# SOC_DISPLAY.net
KiCad netlist of a schematic drawn in Altium Designer
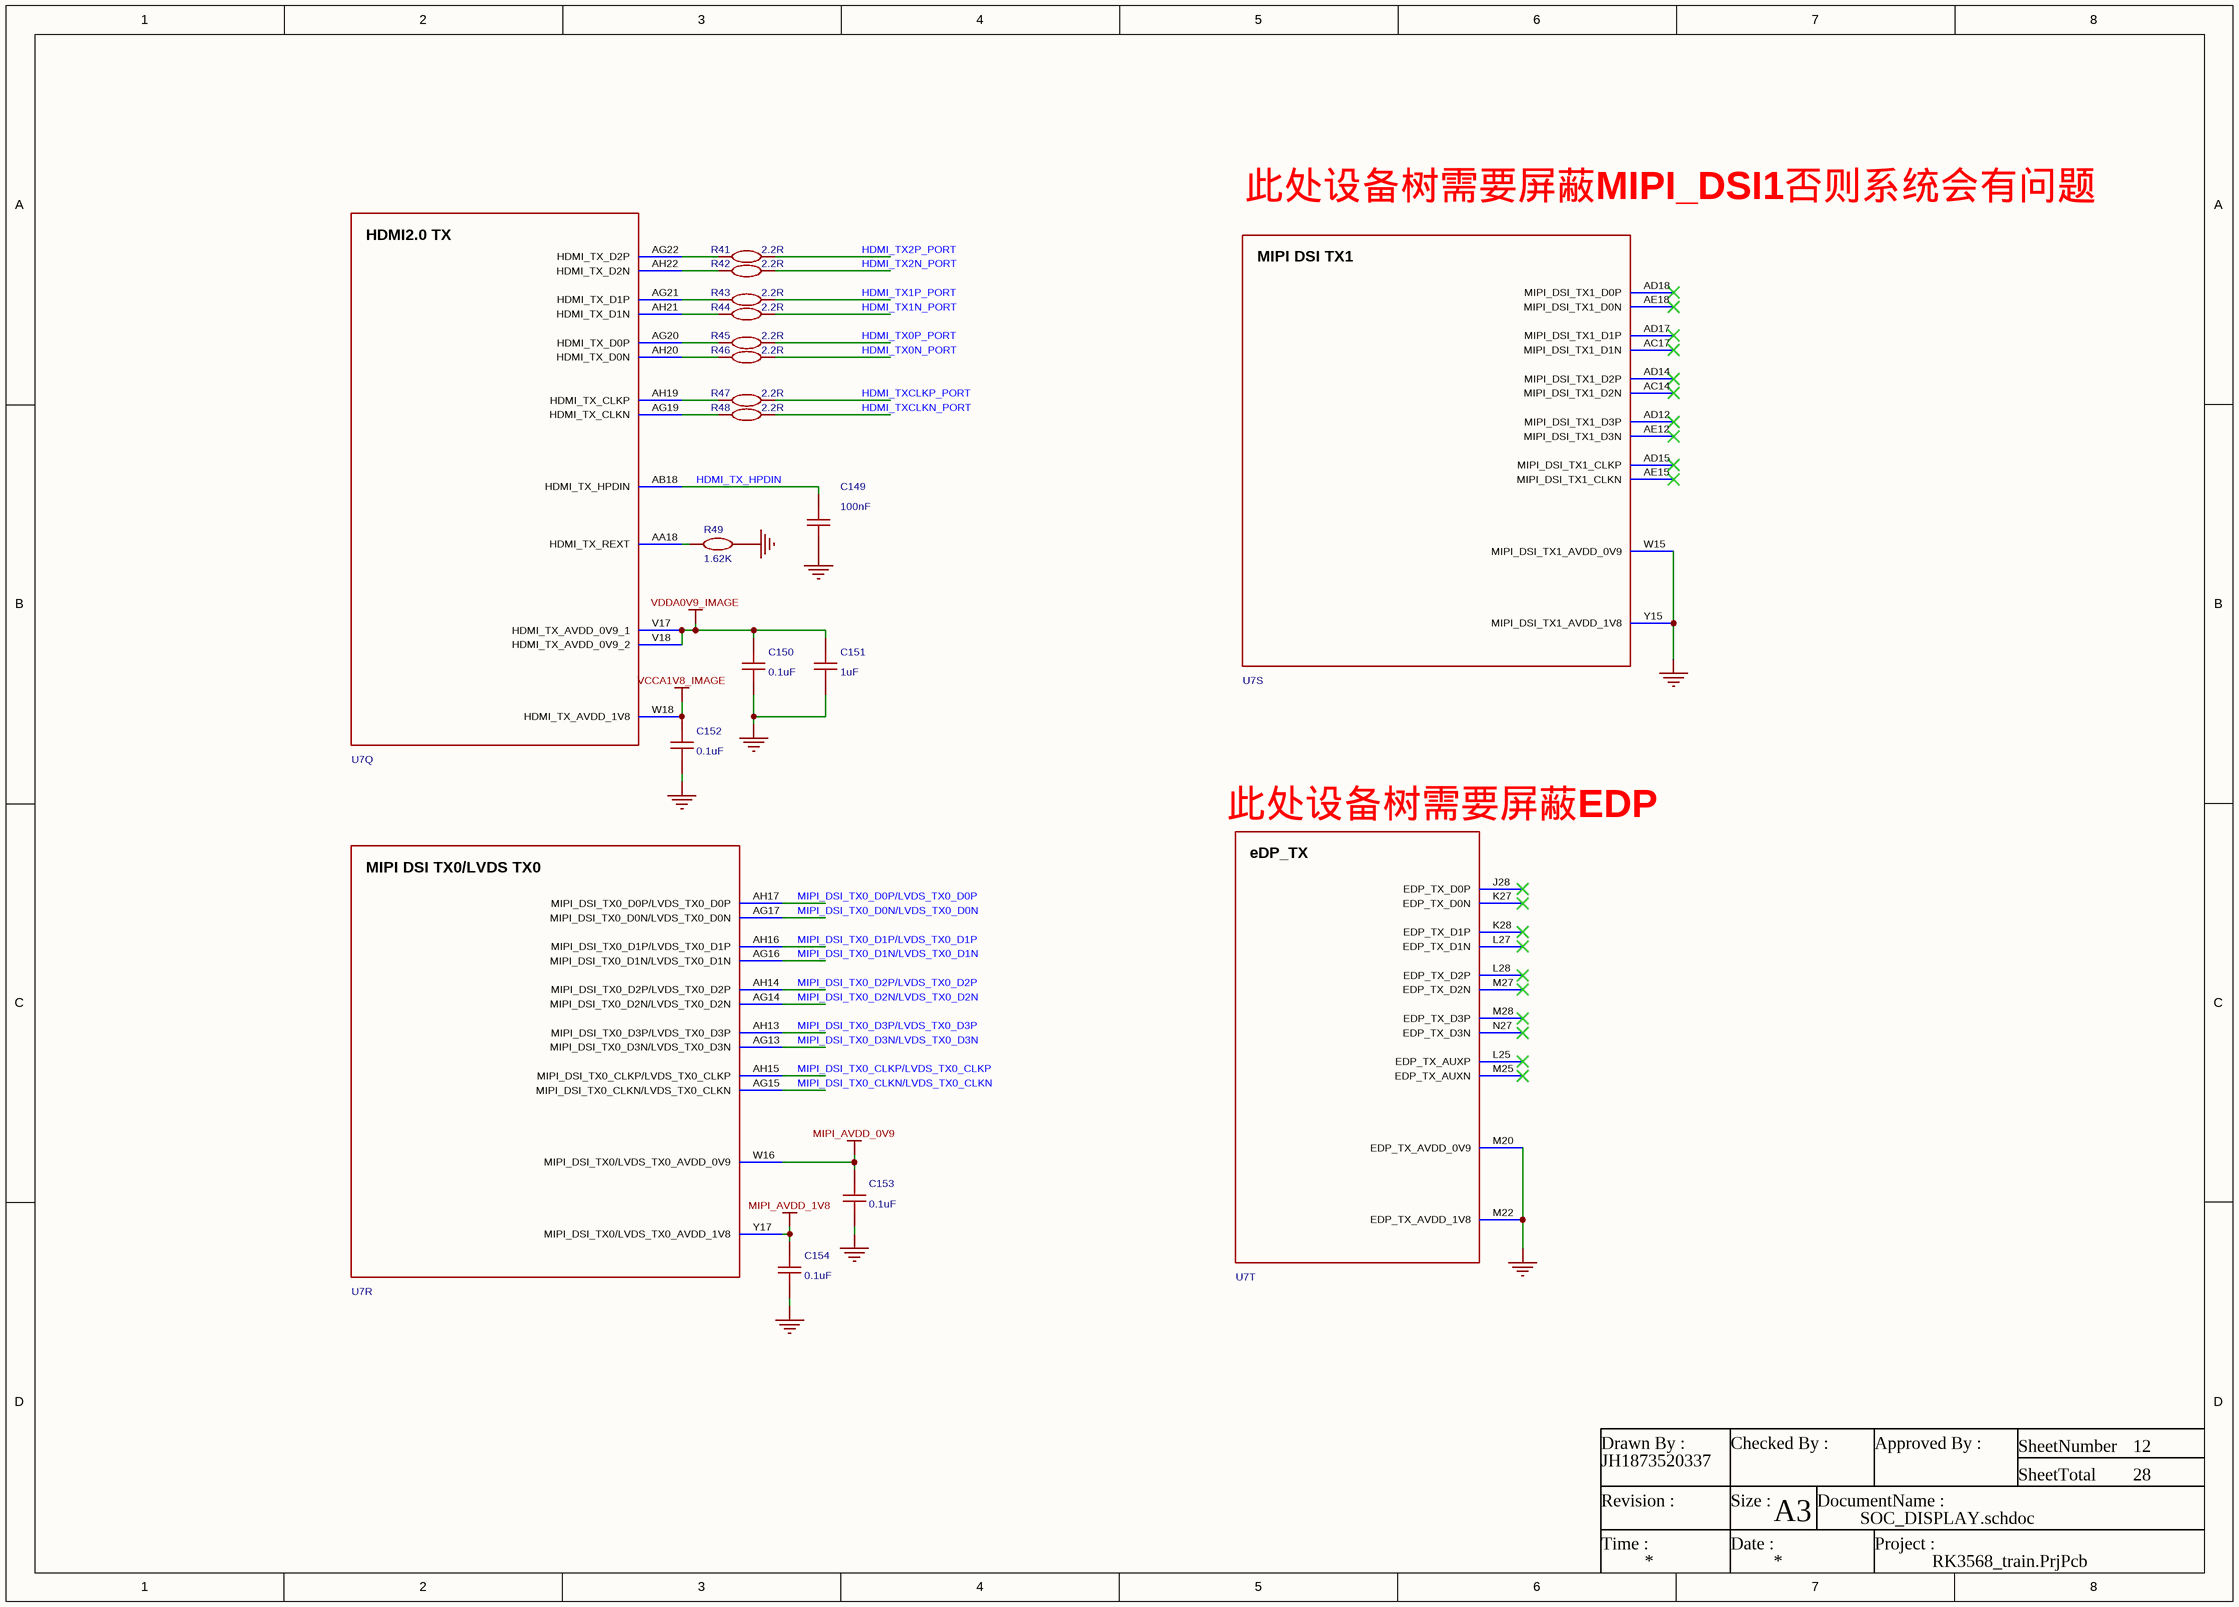
[diagram p0: SOC_DISPLAY.schdoc]

(export (version "E")
  (design (tool "Eeschema 10.0.6"))
  (components
    (comp (ref "C149")
      (value "100nF")
      (footprint "C0201")
      (description "容值:4.7uF;精度:±20%;额定电压:6.3V;温度系数:X5R;")
      (fields
        (field (name "MANUFACTURER") "muRata(村田)")
        (field (name "MANUFACTURERPART") "GRM035R60J475ME15D")
      )
      (libsource (lib "altium-import") (part "root_0_GRM035R60J475ME15D_"))
    )
    (comp (ref "C150")
      (value "0.1uF")
      (footprint "C0201")
      (description "容值:4.7uF;精度:±20%;额定电压:6.3V;温度系数:X5R;")
      (fields
        (field (name "MANUFACTURER") "muRata(村田)")
        (field (name "MANUFACTURERPART") "GRM035R60J475ME15D")
      )
      (libsource (lib "altium-import") (part "root_0_GRM035R60J475ME15D_"))
    )
    (comp (ref "C151")
      (value "1uF")
      (footprint "C0201")
      (description "容值:4.7uF;精度:±20%;额定电压:6.3V;温度系数:X5R;")
      (fields
        (field (name "MANUFACTURER") "muRata(村田)")
        (field (name "MANUFACTURERPART") "GRM035R60J475ME15D")
      )
      (libsource (lib "altium-import") (part "root_0_GRM035R60J475ME15D_"))
    )
    (comp (ref "C152")
      (value "0.1uF")
      (footprint "C0201")
      (description "容值:4.7uF;精度:±20%;额定电压:6.3V;温度系数:X5R;")
      (fields
        (field (name "MANUFACTURER") "muRata(村田)")
        (field (name "MANUFACTURERPART") "GRM035R60J475ME15D")
      )
      (libsource (lib "altium-import") (part "root_0_GRM035R60J475ME15D_"))
    )
    (comp (ref "C153")
      (value "0.1uF")
      (footprint "C0201")
      (description "容值:4.7uF;精度:±20%;额定电压:6.3V;温度系数:X5R;")
      (fields
        (field (name "MANUFACTURER") "muRata(村田)")
        (field (name "MANUFACTURERPART") "GRM035R60J475ME15D")
      )
      (libsource (lib "altium-import") (part "root_0_GRM035R60J475ME15D_"))
    )
    (comp (ref "C154")
      (value "0.1uF")
      (footprint "C0201")
      (description "容值:4.7uF;精度:±20%;额定电压:6.3V;温度系数:X5R;")
      (fields
        (field (name "MANUFACTURER") "muRata(村田)")
        (field (name "MANUFACTURERPART") "GRM035R60J475ME15D")
      )
      (libsource (lib "altium-import") (part "root_0_GRM035R60J475ME15D_"))
    )
    (comp (ref "R41")
      (value "2.2R")
      (footprint "R0201")
      (libsource (lib "altium-import") (part "root_0_Res_0201_"))
    )
    (comp (ref "R42")
      (value "2.2R")
      (footprint "R0201")
      (libsource (lib "altium-import") (part "root_0_Res_0201_"))
    )
    (comp (ref "R43")
      (value "2.2R")
      (footprint "R0201")
      (libsource (lib "altium-import") (part "root_0_Res_0201_"))
    )
    (comp (ref "R44")
      (value "2.2R")
      (footprint "R0201")
      (libsource (lib "altium-import") (part "root_0_Res_0201_"))
    )
    (comp (ref "R45")
      (value "2.2R")
      (footprint "R0201")
      (libsource (lib "altium-import") (part "root_0_Res_0201_"))
    )
    (comp (ref "R46")
      (value "2.2R")
      (footprint "R0201")
      (libsource (lib "altium-import") (part "root_0_Res_0201_"))
    )
    (comp (ref "R47")
      (value "2.2R")
      (footprint "R0201")
      (libsource (lib "altium-import") (part "root_0_Res_0201_"))
    )
    (comp (ref "R48")
      (value "2.2R")
      (footprint "R0201")
      (libsource (lib "altium-import") (part "root_0_Res_0201_"))
    )
    (comp (ref "R49")
      (value "1.62K")
      (footprint "R0201")
      (libsource (lib "altium-import") (part "root_0_Res_0201_"))
    )
    (comp (ref "U7")
      (value "RK3568")
      (footprint "BGA-636_L19.0-W19.0-P0.65-BL")
      (libsource (lib "altium-import") (part "root_0_RK3568_"))
    )
  )
  (nets
    (net (code "1") (name "/HDMI_TX0N_PORT") (class "Default")
      (node (ref "R46") (pin "2") (pinfunction "2_2") (pintype "passive"))
    )
    (net (code "2") (name "/HDMI_TX0P_PORT") (class "Default")
      (node (ref "R45") (pin "2") (pinfunction "2_2") (pintype "passive"))
    )
    (net (code "3") (name "/HDMI_TX1N_PORT") (class "Default")
      (node (ref "R44") (pin "2") (pinfunction "2_2") (pintype "passive"))
    )
    (net (code "4") (name "/HDMI_TX1P_PORT") (class "Default")
      (node (ref "R43") (pin "2") (pinfunction "2_2") (pintype "passive"))
    )
    (net (code "5") (name "/HDMI_TX2N_PORT") (class "Default")
      (node (ref "R42") (pin "2") (pinfunction "2_2") (pintype "passive"))
    )
    (net (code "6") (name "/HDMI_TX2P_PORT") (class "Default")
      (node (ref "R41") (pin "2") (pinfunction "2_2") (pintype "passive"))
    )
    (net (code "7") (name "/HDMI_TXCLKN_PORT") (class "Default")
      (node (ref "R48") (pin "2") (pinfunction "2_2") (pintype "passive"))
    )
    (net (code "8") (name "/HDMI_TXCLKP_PORT") (class "Default")
      (node (ref "R47") (pin "2") (pinfunction "2_2") (pintype "passive"))
    )
    (net (code "9") (name "/HDMI_TX_HPDIN") (class "Default")
      (node (ref "C149") (pin "2") (pinfunction "2_2") (pintype "passive"))
      (node (ref "U7") (pin "AB18") (pinfunction "HDMI_TX_HPDIN_AB18") (pintype "passive"))
    )
    (net (code "10") (name "/MIPI_DSI_TX0_CLKN{slash}LVDS_TX0_CLKN") (class "Default")
      (node (ref "U7") (pin "AG15") (pinfunction "MIPI_DSI_TX0_CLKN/LVDS_TX0_CLKN_AG15") (pintype "passive"))
    )
    (net (code "11") (name "/MIPI_DSI_TX0_CLKP{slash}LVDS_TX0_CLKP") (class "Default")
      (node (ref "U7") (pin "AH15") (pinfunction "MIPI_DSI_TX0_CLKP/LVDS_TX0_CLKP_AH15") (pintype "passive"))
    )
    (net (code "12") (name "/MIPI_DSI_TX0_D0N{slash}LVDS_TX0_D0N") (class "Default")
      (node (ref "U7") (pin "AG17") (pinfunction "MIPI_DSI_TX0_D0N/LVDS_TX0_D0N_AG17") (pintype "passive"))
    )
    (net (code "13") (name "/MIPI_DSI_TX0_D0P{slash}LVDS_TX0_D0P") (class "Default")
      (node (ref "U7") (pin "AH17") (pinfunction "MIPI_DSI_TX0_D0P/LVDS_TX0_D0P_AH17") (pintype "passive"))
    )
    (net (code "14") (name "/MIPI_DSI_TX0_D1N{slash}LVDS_TX0_D1N") (class "Default")
      (node (ref "U7") (pin "AG16") (pinfunction "MIPI_DSI_TX0_D1N/LVDS_TX0_D1N_AG16") (pintype "passive"))
    )
    (net (code "15") (name "/MIPI_DSI_TX0_D1P{slash}LVDS_TX0_D1P") (class "Default")
      (node (ref "U7") (pin "AH16") (pinfunction "MIPI_DSI_TX0_D1P/LVDS_TX0_D1P_AH16") (pintype "passive"))
    )
    (net (code "16") (name "/MIPI_DSI_TX0_D2N{slash}LVDS_TX0_D2N") (class "Default")
      (node (ref "U7") (pin "AG14") (pinfunction "MIPI_DSI_TX0_D2N/LVDS_TX0_D2N_AG14") (pintype "passive"))
    )
    (net (code "17") (name "/MIPI_DSI_TX0_D2P{slash}LVDS_TX0_D2P") (class "Default")
      (node (ref "U7") (pin "AH14") (pinfunction "MIPI_DSI_TX0_D2P/LVDS_TX0_D2P_AH14") (pintype "passive"))
    )
    (net (code "18") (name "/MIPI_DSI_TX0_D3N{slash}LVDS_TX0_D3N") (class "Default")
      (node (ref "U7") (pin "AG13") (pinfunction "MIPI_DSI_TX0_D3N/LVDS_TX0_D3N_AG13") (pintype "passive"))
    )
    (net (code "19") (name "/MIPI_DSI_TX0_D3P{slash}LVDS_TX0_D3P") (class "Default")
      (node (ref "U7") (pin "AH13") (pinfunction "MIPI_DSI_TX0_D3P/LVDS_TX0_D3P_AH13") (pintype "passive"))
    )
    (net (code "20") (name "GND") (class "Default")
      (node (ref "C149") (pin "1") (pinfunction "1_1") (pintype "passive"))
      (node (ref "C150") (pin "1") (pinfunction "1_1") (pintype "passive"))
      (node (ref "C151") (pin "1") (pinfunction "1_1") (pintype "passive"))
      (node (ref "C152") (pin "1") (pinfunction "1_1") (pintype "passive"))
      (node (ref "C153") (pin "1") (pinfunction "1_1") (pintype "passive"))
      (node (ref "C154") (pin "1") (pinfunction "1_1") (pintype "passive"))
      (node (ref "R49") (pin "2") (pinfunction "2_2") (pintype "passive"))
      (node (ref "U7") (pin "M20") (pinfunction "EDP_TX_AVDD_0V9_M20") (pintype "passive"))
      (node (ref "U7") (pin "M22") (pinfunction "EDP_TX_AVDD_1V8_M22") (pintype "passive"))
      (node (ref "U7") (pin "W15") (pinfunction "MIPI_DSI_TX1_AVDD_0V9_W15") (pintype "passive"))
      (node (ref "U7") (pin "Y15") (pinfunction "MIPI_DSI_TX1_AVDD_1V8_Y15") (pintype "passive"))
    )
    (net (code "21") (name "MIPI_AVDD_0V9") (class "Default")
      (node (ref "C153") (pin "2") (pinfunction "2_2") (pintype "passive"))
      (node (ref "U7") (pin "W16") (pinfunction "MIPI_DSI_TX0/LVDS_TX0_AVDD_0V9_W16") (pintype "passive"))
    )
    (net (code "22") (name "MIPI_AVDD_1V8") (class "Default")
      (node (ref "C154") (pin "2") (pinfunction "2_2") (pintype "passive"))
      (node (ref "U7") (pin "Y17") (pinfunction "MIPI_DSI_TX0/LVDS_TX0_AVDD_1V8_Y17") (pintype "passive"))
    )
    (net (code "23") (name "Net-(U7Q-HDMI_TX_CLKN)") (class "Default")
      (node (ref "R48") (pin "1") (pinfunction "1_1") (pintype "passive"))
      (node (ref "U7") (pin "AG19") (pinfunction "HDMI_TX_CLKN_AG19") (pintype "passive"))
    )
    (net (code "24") (name "Net-(U7Q-HDMI_TX_CLKP)") (class "Default")
      (node (ref "R47") (pin "1") (pinfunction "1_1") (pintype "passive"))
      (node (ref "U7") (pin "AH19") (pinfunction "HDMI_TX_CLKP_AH19") (pintype "passive"))
    )
    (net (code "25") (name "Net-(U7Q-HDMI_TX_D0N)") (class "Default")
      (node (ref "R46") (pin "1") (pinfunction "1_1") (pintype "passive"))
      (node (ref "U7") (pin "AH20") (pinfunction "HDMI_TX_D0N_AH20") (pintype "passive"))
    )
    (net (code "26") (name "Net-(U7Q-HDMI_TX_D0P)") (class "Default")
      (node (ref "R45") (pin "1") (pinfunction "1_1") (pintype "passive"))
      (node (ref "U7") (pin "AG20") (pinfunction "HDMI_TX_D0P_AG20") (pintype "passive"))
    )
    (net (code "27") (name "Net-(U7Q-HDMI_TX_D1N)") (class "Default")
      (node (ref "R44") (pin "1") (pinfunction "1_1") (pintype "passive"))
      (node (ref "U7") (pin "AH21") (pinfunction "HDMI_TX_D1N_AH21") (pintype "passive"))
    )
    (net (code "28") (name "Net-(U7Q-HDMI_TX_D1P)") (class "Default")
      (node (ref "R43") (pin "1") (pinfunction "1_1") (pintype "passive"))
      (node (ref "U7") (pin "AG21") (pinfunction "HDMI_TX_D1P_AG21") (pintype "passive"))
    )
    (net (code "29") (name "Net-(U7Q-HDMI_TX_D2N)") (class "Default")
      (node (ref "R42") (pin "1") (pinfunction "1_1") (pintype "passive"))
      (node (ref "U7") (pin "AH22") (pinfunction "HDMI_TX_D2N_AH22") (pintype "passive"))
    )
    (net (code "30") (name "Net-(U7Q-HDMI_TX_D2P)") (class "Default")
      (node (ref "R41") (pin "1") (pinfunction "1_1") (pintype "passive"))
      (node (ref "U7") (pin "AG22") (pinfunction "HDMI_TX_D2P_AG22") (pintype "passive"))
    )
    (net (code "31") (name "Net-(U7Q-HDMI_TX_REXT)") (class "Default")
      (node (ref "R49") (pin "1") (pinfunction "1_1") (pintype "passive"))
      (node (ref "U7") (pin "AA18") (pinfunction "HDMI_TX_REXT_AA18") (pintype "passive"))
    )
    (net (code "32") (name "VCCA1V8_IMAGE") (class "Default")
      (node (ref "C152") (pin "2") (pinfunction "2_2") (pintype "passive"))
      (node (ref "U7") (pin "W18") (pinfunction "HDMI_TX_AVDD_1V8_W18") (pintype "passive"))
    )
    (net (code "33") (name "VDDA0V9_IMAGE") (class "Default")
      (node (ref "C150") (pin "2") (pinfunction "2_2") (pintype "passive"))
      (node (ref "C151") (pin "2") (pinfunction "2_2") (pintype "passive"))
      (node (ref "U7") (pin "V17") (pinfunction "HDMI_TX_AVDD_0V9_1_V17") (pintype "passive"))
      (node (ref "U7") (pin "V18") (pinfunction "HDMI_TX_AVDD_0V9_2_V18") (pintype "passive"))
    )
    (net (code "34") (name "unconnected-(U7S-MIPI_DSI_TX1_CLKN-PadAE15)") (class "Default")
      (node (ref "U7") (pin "AE15") (pinfunction "MIPI_DSI_TX1_CLKN_AE15") (pintype "passive+no_connect"))
    )
    (net (code "35") (name "unconnected-(U7S-MIPI_DSI_TX1_CLKP-PadAD15)") (class "Default")
      (node (ref "U7") (pin "AD15") (pinfunction "MIPI_DSI_TX1_CLKP_AD15") (pintype "passive+no_connect"))
    )
    (net (code "36") (name "unconnected-(U7S-MIPI_DSI_TX1_D0N-PadAE18)") (class "Default")
      (node (ref "U7") (pin "AE18") (pinfunction "MIPI_DSI_TX1_D0N_AE18") (pintype "passive+no_connect"))
    )
    (net (code "37") (name "unconnected-(U7S-MIPI_DSI_TX1_D0P-PadAD18)") (class "Default")
      (node (ref "U7") (pin "AD18") (pinfunction "MIPI_DSI_TX1_D0P_AD18") (pintype "passive+no_connect"))
    )
    (net (code "38") (name "unconnected-(U7S-MIPI_DSI_TX1_D1N-PadAC17)") (class "Default")
      (node (ref "U7") (pin "AC17") (pinfunction "MIPI_DSI_TX1_D1N_AC17") (pintype "passive+no_connect"))
    )
    (net (code "39") (name "unconnected-(U7S-MIPI_DSI_TX1_D1P-PadAD17)") (class "Default")
      (node (ref "U7") (pin "AD17") (pinfunction "MIPI_DSI_TX1_D1P_AD17") (pintype "passive+no_connect"))
    )
    (net (code "40") (name "unconnected-(U7S-MIPI_DSI_TX1_D2N-PadAC14)") (class "Default")
      (node (ref "U7") (pin "AC14") (pinfunction "MIPI_DSI_TX1_D2N_AC14") (pintype "passive+no_connect"))
    )
    (net (code "41") (name "unconnected-(U7S-MIPI_DSI_TX1_D2P-PadAD14)") (class "Default")
      (node (ref "U7") (pin "AD14") (pinfunction "MIPI_DSI_TX1_D2P_AD14") (pintype "passive+no_connect"))
    )
    (net (code "42") (name "unconnected-(U7S-MIPI_DSI_TX1_D3N-PadAE12)") (class "Default")
      (node (ref "U7") (pin "AE12") (pinfunction "MIPI_DSI_TX1_D3N_AE12") (pintype "passive+no_connect"))
    )
    (net (code "43") (name "unconnected-(U7S-MIPI_DSI_TX1_D3P-PadAD12)") (class "Default")
      (node (ref "U7") (pin "AD12") (pinfunction "MIPI_DSI_TX1_D3P_AD12") (pintype "passive+no_connect"))
    )
    (net (code "44") (name "unconnected-(U7T-EDP_TX_AUXN-PadM25)") (class "Default")
      (node (ref "U7") (pin "M25") (pinfunction "EDP_TX_AUXN_M25") (pintype "passive+no_connect"))
    )
    (net (code "45") (name "unconnected-(U7T-EDP_TX_AUXP-PadL25)") (class "Default")
      (node (ref "U7") (pin "L25") (pinfunction "EDP_TX_AUXP_L25") (pintype "passive+no_connect"))
    )
    (net (code "46") (name "unconnected-(U7T-EDP_TX_D0N-PadK27)") (class "Default")
      (node (ref "U7") (pin "K27") (pinfunction "EDP_TX_D0N_K27") (pintype "passive+no_connect"))
    )
    (net (code "47") (name "unconnected-(U7T-EDP_TX_D0P-PadJ28)") (class "Default")
      (node (ref "U7") (pin "J28") (pinfunction "EDP_TX_D0P_J28") (pintype "passive+no_connect"))
    )
    (net (code "48") (name "unconnected-(U7T-EDP_TX_D1N-PadL27)") (class "Default")
      (node (ref "U7") (pin "L27") (pinfunction "EDP_TX_D1N_L27") (pintype "passive+no_connect"))
    )
    (net (code "49") (name "unconnected-(U7T-EDP_TX_D1P-PadK28)") (class "Default")
      (node (ref "U7") (pin "K28") (pinfunction "EDP_TX_D1P_K28") (pintype "passive+no_connect"))
    )
    (net (code "50") (name "unconnected-(U7T-EDP_TX_D2N-PadM27)") (class "Default")
      (node (ref "U7") (pin "M27") (pinfunction "EDP_TX_D2N_M27") (pintype "passive+no_connect"))
    )
    (net (code "51") (name "unconnected-(U7T-EDP_TX_D2P-PadL28)") (class "Default")
      (node (ref "U7") (pin "L28") (pinfunction "EDP_TX_D2P_L28") (pintype "passive+no_connect"))
    )
    (net (code "52") (name "unconnected-(U7T-EDP_TX_D3N-PadN27)") (class "Default")
      (node (ref "U7") (pin "N27") (pinfunction "EDP_TX_D3N_N27") (pintype "passive+no_connect"))
    )
    (net (code "53") (name "unconnected-(U7T-EDP_TX_D3P-PadM28)") (class "Default")
      (node (ref "U7") (pin "M28") (pinfunction "EDP_TX_D3P_M28") (pintype "passive+no_connect"))
    )
  )
)
